# P6_FilterMode.net
KiCad netlist of a schematic drawn in Altium Designer
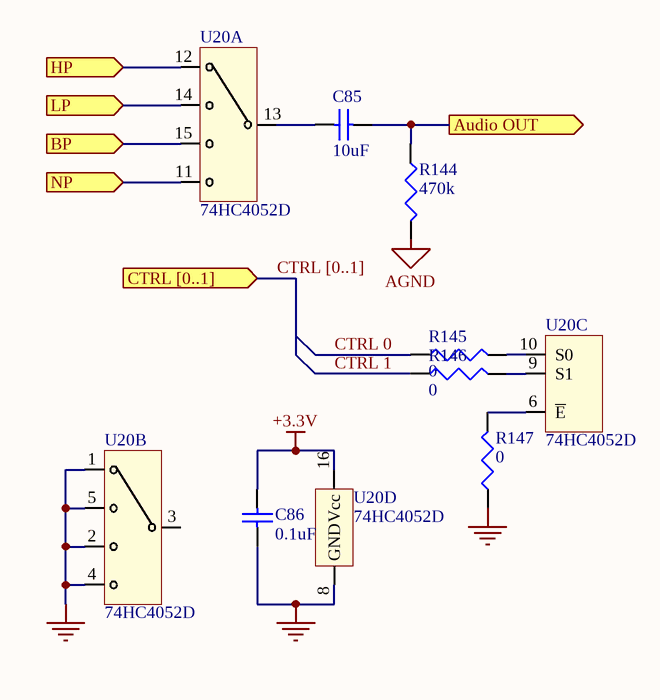
[diagram p0: P6_FilterMode.SchDoc]

(export (version "E")
  (design (tool "Eeschema 10.0.6"))
  (components
    (comp (ref "C85")
      (value "10uF")
      (footprint "CAP 0603 (1608 metric)")
      (description "Capacitor (Semiconductor SIM Model)")
      (libsource (lib "Miscellaneous Devices") (part "Cap Semi"))
    )
    (comp (ref "C86")
      (value "0.1uF")
      (footprint "CAP 0603 (1608 metric)")
      (description "Capacitor (Semiconductor SIM Model)")
      (libsource (lib "Miscellaneous Devices") (part "Cap Semi"))
    )
    (comp (ref "R144")
      (value "470k")
      (footprint "RES 0603 (1608 metric)")
      (description "Resistor")
      (libsource (lib "Miscellaneous Devices") (part "Res3"))
    )
    (comp (ref "R145")
      (value "0")
      (footprint "RES 0603 (1608 metric)")
      (description "Resistor")
      (libsource (lib "Miscellaneous Devices") (part "Res3"))
    )
    (comp (ref "R146")
      (value "0")
      (footprint "RES 0603 (1608 metric)")
      (description "Resistor")
      (libsource (lib "Miscellaneous Devices") (part "Res3"))
    )
    (comp (ref "R147")
      (value "0")
      (footprint "RES 0603 (1608 metric)")
      (description "Resistor")
      (libsource (lib "Miscellaneous Devices") (part "Res3"))
    )
    (comp (ref "U20")
      (value "74HC4052D")
      (description "Dual 4:1 Multiplexer")
      (libsource (lib "FilterPoC") (part "74HC4052D"))
    )
  )
  (nets
    (net (code "1") (name "+3.3V") (class "Default")
      (node (ref "C86") (pin "1") (pinfunction "1_1") (pintype "passive"))
      (node (ref "U20") (pin "16") (pinfunction "Vcc_16") (pintype "power_in"))
    )
    (net (code "2") (name "/Audio OUT") (class "Default")
      (node (ref "C85") (pin "1") (pinfunction "1_1") (pintype "passive"))
      (node (ref "R144") (pin "1") (pinfunction "1_1") (pintype "passive"))
    )
    (net (code "3") (name "/BP") (class "Default")
      (node (ref "U20") (pin "15") (pinfunction "1Y2_15") (pintype "passive"))
    )
    (net (code "4") (name "/CTRL 0") (class "Default")
      (node (ref "R145") (pin "1") (pinfunction "1_1") (pintype "passive"))
    )
    (net (code "5") (name "/CTRL 1") (class "Default")
      (node (ref "R146") (pin "1") (pinfunction "1_1") (pintype "passive"))
    )
    (net (code "6") (name "/HP") (class "Default")
      (node (ref "U20") (pin "12") (pinfunction "1Y0_12") (pintype "passive"))
    )
    (net (code "7") (name "/LP") (class "Default")
      (node (ref "U20") (pin "14") (pinfunction "1Y1_14") (pintype "passive"))
    )
    (net (code "8") (name "/NP") (class "Default")
      (node (ref "U20") (pin "11") (pinfunction "1Y3_11") (pintype "passive"))
    )
    (net (code "10") (name "AGND") (class "Default")
      (node (ref "R144") (pin "2") (pinfunction "2_2") (pintype "passive"))
    )
    (net (code "11") (name "GND") (class "Default")
      (node (ref "C86") (pin "2") (pinfunction "2_2") (pintype "passive"))
      (node (ref "R147") (pin "1") (pinfunction "1_1") (pintype "passive"))
      (node (ref "U20") (pin "1") (pinfunction "2Y0_1") (pintype "passive"))
      (node (ref "U20") (pin "2") (pinfunction "2Y2_2") (pintype "passive"))
      (node (ref "U20") (pin "4") (pinfunction "2Y3_4") (pintype "passive"))
      (node (ref "U20") (pin "5") (pinfunction "2Y1_5") (pintype "passive"))
      (node (ref "U20") (pin "8") (pinfunction "GND_8") (pintype "power_in"))
    )
    (net (code "12") (name "Net-(U20A-1Z)") (class "Default")
      (node (ref "C85") (pin "2") (pinfunction "2_2") (pintype "passive"))
      (node (ref "U20") (pin "13") (pinfunction "1Z_13") (pintype "passive"))
    )
    (net (code "13") (name "Net-(U20C-S0)") (class "Default")
      (node (ref "R145") (pin "2") (pinfunction "2_2") (pintype "passive"))
      (node (ref "U20") (pin "10") (pinfunction "S0_10") (pintype "passive"))
    )
    (net (code "14") (name "Net-(U20C-S1)") (class "Default")
      (node (ref "R146") (pin "2") (pinfunction "2_2") (pintype "passive"))
      (node (ref "U20") (pin "9") (pinfunction "S1_9") (pintype "passive"))
    )
    (net (code "15") (name "Net-(U20C-~{E})") (class "Default")
      (node (ref "R147") (pin "2") (pinfunction "2_2") (pintype "passive"))
      (node (ref "U20") (pin "6") (pinfunction "~{E}_6") (pintype "passive"))
    )
    (net (code "16") (name "unconnected-(U20B-2Z-Pad3)") (class "Default")
      (node (ref "U20") (pin "3") (pinfunction "2Z_3") (pintype "passive"))
    )
  )
)
